# MIXR_Processing_-_ESP32.net
KiCad netlist of a schematic drawn in Altium Designer
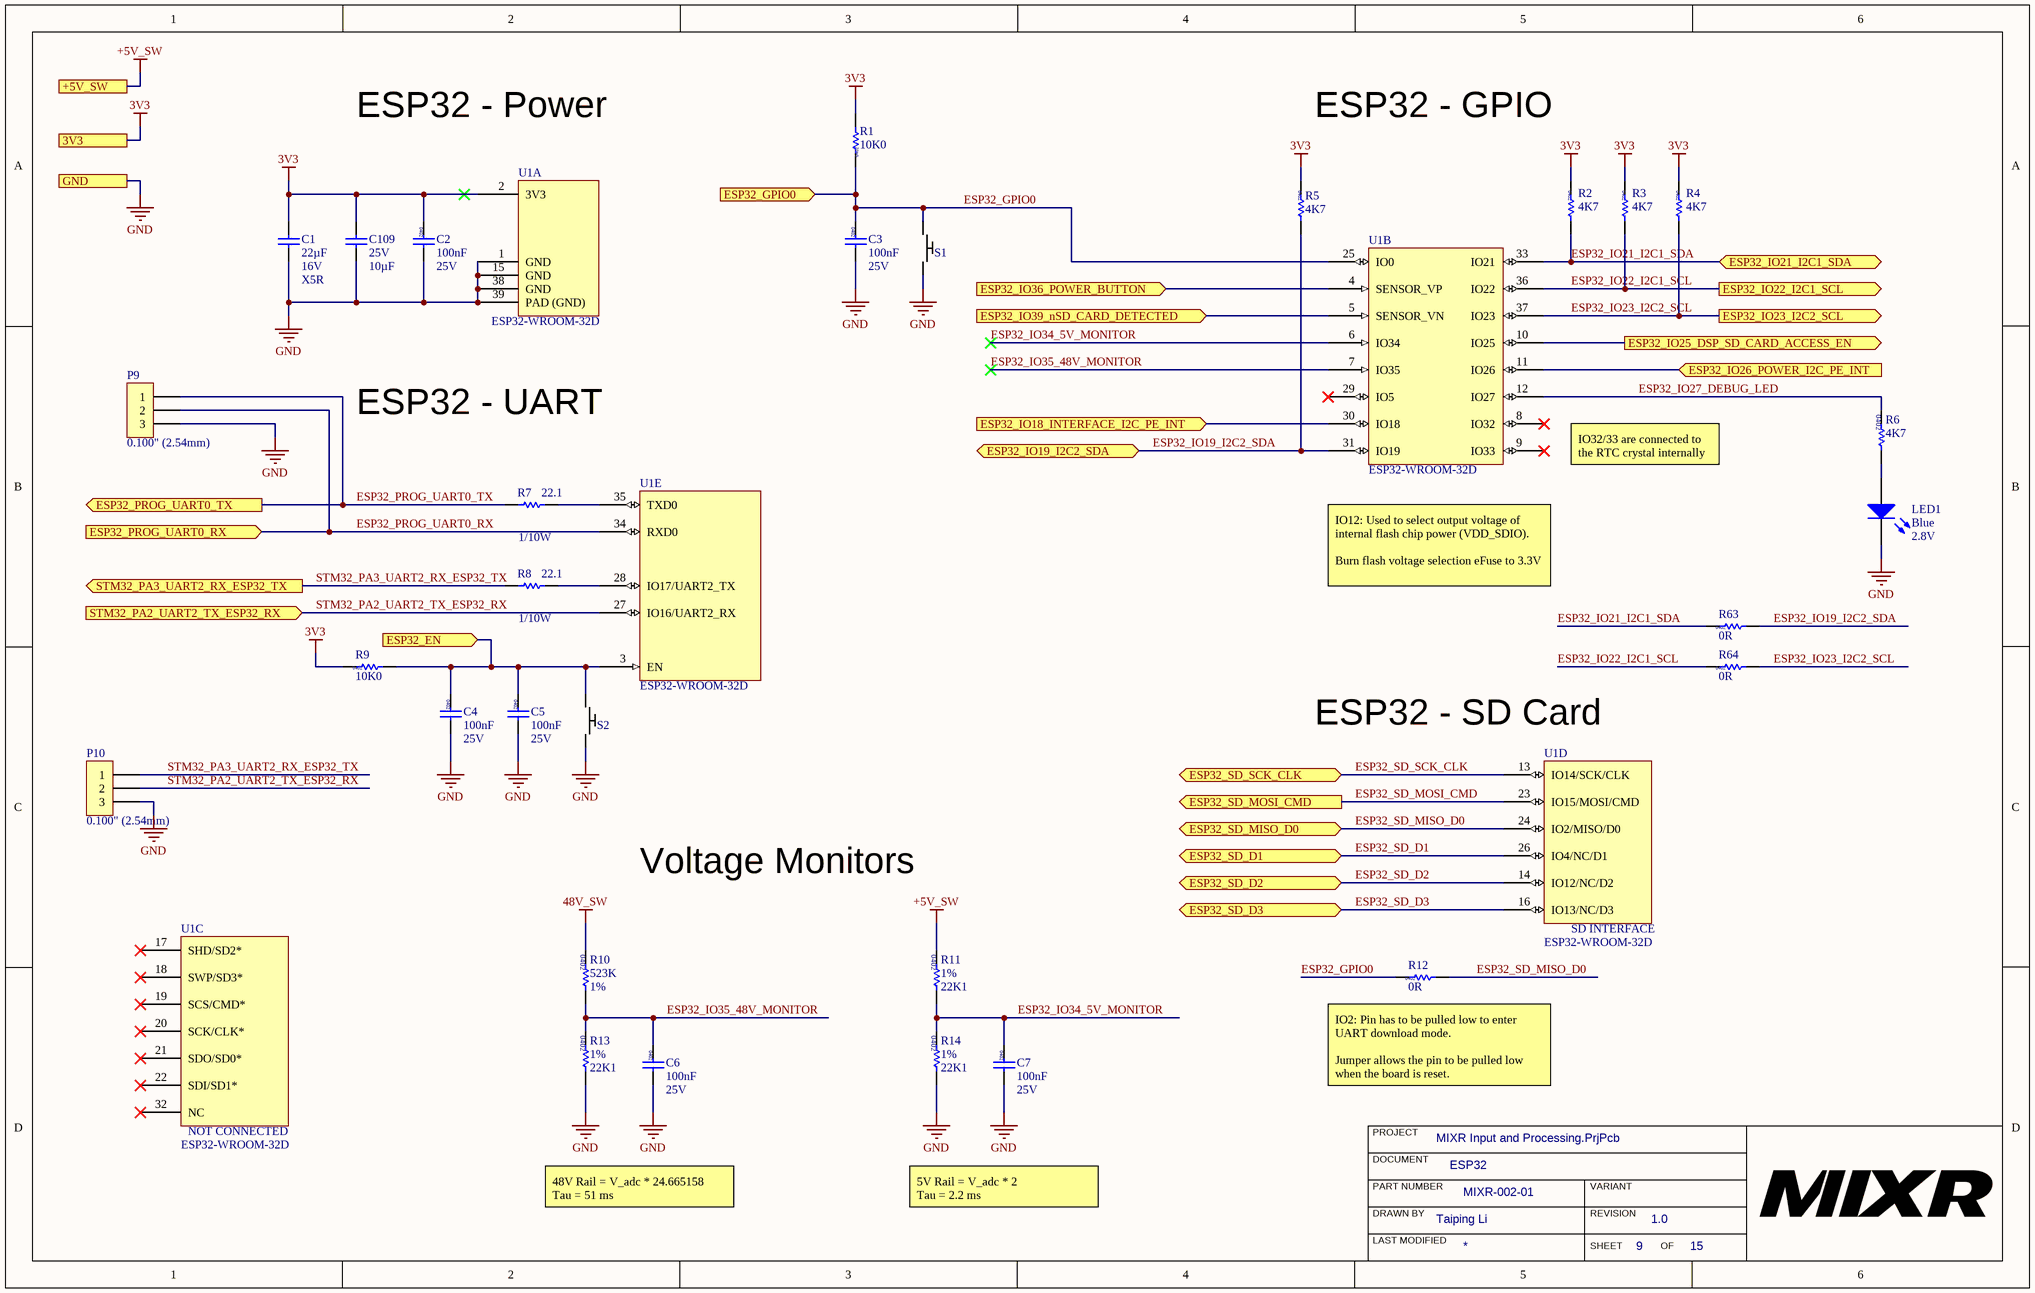
[diagram p0: MIXR Processing - ESP32.SchDoc]

(export (version "E")
  (design (tool "Eeschema 10.0.6"))
  (components
    (comp (ref "C1")
      (value "CAP CER 22UF 16V ±20% X5R 1210")
      (footprint "CAP, 1210")
      (description "22µF ±20% 16V Ceramic Capacitor X5R 1210 (3225 Metric)")
      (fields
        (field (name "TOLERANCE") "±20%")
        (field (name "CAPACITANCE") "22µF")
        (field (name "VOLTAGE") "16V")
        (field (name "TEMPERATURE COEFFICIENT") "X5R")
      )
      (libsource (lib "Schematic Diagrams") (part "CAP CER 22UF 16V ±20% X5R 1210"))
    )
    (comp (ref "C2")
      (value "CAP CER 0.1UF 16V X7R 0402")
      (footprint "CAP 0402")
      (description "Cap Ceramic 0.1uF 25V X7R 10% SMD 0402 125C Paper T/R")
      (fields
        (field (name "TOLERANCE") "10%")
        (field (name "CAPACITANCE") "100nF")
        (field (name "VOLTAGE") "25V")
        (field (name "MANUFACTURER") "Murata")
      )
      (libsource (lib "Schematic Diagrams") (part "CAP CER 0.1UF 16V X7R 0402"))
    )
    (comp (ref "C3")
      (value "CAP CER 0.1UF 16V X7R 0402")
      (footprint "CAP 0402")
      (description "Cap Ceramic 0.1uF 25V X7R 10% SMD 0402 125C Paper T/R")
      (fields
        (field (name "TOLERANCE") "10%")
        (field (name "CAPACITANCE") "100nF")
        (field (name "VOLTAGE") "25V")
        (field (name "MANUFACTURER") "Murata")
      )
      (libsource (lib "Schematic Diagrams") (part "CAP CER 0.1UF 16V X7R 0402"))
    )
    (comp (ref "C4")
      (value "CAP CER 0.1UF 16V X7R 0402")
      (footprint "CAP 0402")
      (description "Cap Ceramic 0.1uF 25V X7R 10% SMD 0402 125C Paper T/R")
      (fields
        (field (name "TOLERANCE") "10%")
        (field (name "CAPACITANCE") "100nF")
        (field (name "VOLTAGE") "25V")
        (field (name "MANUFACTURER") "Murata")
      )
      (libsource (lib "Schematic Diagrams") (part "CAP CER 0.1UF 16V X7R 0402"))
    )
    (comp (ref "C5")
      (value "CAP CER 0.1UF 16V X7R 0402")
      (footprint "CAP 0402")
      (description "Cap Ceramic 0.1uF 25V X7R 10% SMD 0402 125C Paper T/R")
      (fields
        (field (name "TOLERANCE") "10%")
        (field (name "CAPACITANCE") "100nF")
        (field (name "VOLTAGE") "25V")
        (field (name "MANUFACTURER") "Murata")
      )
      (libsource (lib "Schematic Diagrams") (part "CAP CER 0.1UF 16V X7R 0402"))
    )
    (comp (ref "C6")
      (value "CAP CER 0.1UF 16V X7R 0402")
      (footprint "CAP 0402")
      (description "Cap Ceramic 0.1uF 25V X7R 10% SMD 0402 125C Paper T/R")
      (fields
        (field (name "TOLERANCE") "10%")
        (field (name "CAPACITANCE") "100nF")
        (field (name "VOLTAGE") "25V")
        (field (name "MANUFACTURER") "Murata")
      )
      (libsource (lib "Schematic Diagrams") (part "CAP CER 0.1UF 16V X7R 0402"))
    )
    (comp (ref "C7")
      (value "CAP CER 0.1UF 16V X7R 0402")
      (footprint "CAP 0402")
      (description "Cap Ceramic 0.1uF 25V X7R 10% SMD 0402 125C Paper T/R")
      (fields
        (field (name "TOLERANCE") "10%")
        (field (name "CAPACITANCE") "100nF")
        (field (name "VOLTAGE") "25V")
        (field (name "MANUFACTURER") "Murata")
      )
      (libsource (lib "Schematic Diagrams") (part "CAP CER 0.1UF 16V X7R 0402"))
    )
    (comp (ref "C109")
      (value "CAP CER 10uF 25V 10% X5R 0805")
      (footprint "CAP, 0805")
      (description "10µF ±10% 25V Ceramic Capacitor X5R 0805 (2012 Metric)")
      (fields
        (field (name "MANUFACTURER") "Murata Electronics North America")
        (field (name "MANUFACTURER PART NUMBER") "GRM21BR61E106KA73L")
        (field (name "VOLTAGE - RATED") "25V")
        (field (name "CAPACITANCE") "10µF")
      )
      (libsource (lib "Schematic Diagrams") (part "CAP CER 10uF 25V 10% X5R 0805"))
    )
    (comp (ref "LED1")
      (value "LED BLUE CLEAR 2.8V 0603")
      (footprint "LED_0603")
      (description "Blue 470nm LED Indication - Discrete 2.8V 0603 (1608 Metric)")
      (fields (field (name "COLOR") "Blue") (field (name "VOLTAGE - FORWARD (VF) (TYP)") "2.8V"))
      (libsource (lib "Schematic Diagrams") (part "LED BLUE CLEAR 2.8V 0603"))
    )
    (comp (ref "P9")
      (value "CONN 3POS HEADR MALE 0.1\"")
      (footprint "CONN, 3POS 0.100\" Header, 1 ROW")
      (description "3 Positions Header Connector 0.100\" (2.54mm) Through Hole Gold")
      (fields (field (name "VOLTAGE") "250V") (field (name "PITCH - MATING") "0.100\" (2.54mm)"))
      (libsource (lib "Schematic Diagrams") (part "CONN 3POS HEADR MALE 0.1{dblquote}"))
    )
    (comp (ref "P10")
      (value "CONN 3POS HEADR MALE 0.1\"")
      (footprint "CONN, 3POS 0.100\" Header, 1 ROW")
      (description "3 Positions Header Connector 0.100\" (2.54mm) Through Hole Gold")
      (fields (field (name "VOLTAGE") "250V") (field (name "PITCH - MATING") "0.100\" (2.54mm)"))
      (libsource (lib "Schematic Diagrams") (part "CONN 3POS HEADR MALE 0.1{dblquote}"))
    )
    (comp (ref "R1")
      (value "RES 10K OHM 1% 1/16W 0402")
      (footprint "RES 0402")
      (description "Surface Mount Thick Film Resistor, Rc Series, 10 Kohm, 62.5 Mw, - 1%, 50 V, 0402 [1005 Metric]")
      (fields
        (field (name "TOLERANCE") "1%")
        (field (name "RESISTANCE") "10K0")
        (field (name "MANUFACTURER") "Yageo")
      )
      (libsource (lib "Schematic Diagrams") (part "RES 10K OHM 1% 1/16W 0402"))
    )
    (comp (ref "R2")
      (value "RES 4.7K OHM 1% 1/10W 0402")
      (footprint "RES 0402")
      (description "YAGEO (PHYCOMP) - RC0402FR-074K7L - RES, THICK FILM, 4K7, 1%, 0.063W, 0402")
      (fields
        (field (name "TOLERANCE") "1%")
        (field (name "MANUFACTURER") "Yageo")
        (field (name "RESISTANCE") "4K7")
      )
      (libsource (lib "Schematic Diagrams") (part "RES 4.7K OHM 1% 1/10W 0402"))
    )
    (comp (ref "R3")
      (value "RES 4.7K OHM 1% 1/10W 0402")
      (footprint "RES 0402")
      (description "YAGEO (PHYCOMP) - RC0402FR-074K7L - RES, THICK FILM, 4K7, 1%, 0.063W, 0402")
      (fields
        (field (name "TOLERANCE") "1%")
        (field (name "MANUFACTURER") "Yageo")
        (field (name "RESISTANCE") "4K7")
      )
      (libsource (lib "Schematic Diagrams") (part "RES 4.7K OHM 1% 1/10W 0402"))
    )
    (comp (ref "R4")
      (value "RES 4.7K OHM 1% 1/10W 0402")
      (footprint "RES 0402")
      (description "YAGEO (PHYCOMP) - RC0402FR-074K7L - RES, THICK FILM, 4K7, 1%, 0.063W, 0402")
      (fields
        (field (name "TOLERANCE") "1%")
        (field (name "MANUFACTURER") "Yageo")
        (field (name "RESISTANCE") "4K7")
      )
      (libsource (lib "Schematic Diagrams") (part "RES 4.7K OHM 1% 1/10W 0402"))
    )
    (comp (ref "R5")
      (value "RES 4.7K OHM 1% 1/10W 0402")
      (footprint "RES 0402")
      (description "YAGEO (PHYCOMP) - RC0402FR-074K7L - RES, THICK FILM, 4K7, 1%, 0.063W, 0402")
      (fields
        (field (name "TOLERANCE") "1%")
        (field (name "MANUFACTURER") "Yageo")
        (field (name "RESISTANCE") "4K7")
      )
      (libsource (lib "Schematic Diagrams") (part "RES 4.7K OHM 1% 1/10W 0402"))
    )
    (comp (ref "R6")
      (value "RES 4.7K OHM 1% 1/10W 0402")
      (footprint "RES 0402")
      (description "YAGEO (PHYCOMP) - RC0402FR-074K7L - RES, THICK FILM, 4K7, 1%, 0.063W, 0402")
      (fields
        (field (name "TOLERANCE") "1%")
        (field (name "MANUFACTURER") "Yageo")
        (field (name "RESISTANCE") "4K7")
      )
      (libsource (lib "Schematic Diagrams") (part "RES 4.7K OHM 1% 1/10W 0402"))
    )
    (comp (ref "R7")
      (value "RES 22.1 OHM 1% 1/10W 0603")
      (footprint "RES, 0603")
      (description "22.1 Ohm ±1% 0.1W, 1/10W Chip Resistor 0603 (1608 Metric) Moisture Resistant Thick Film")
      (fields
        (field (name "TOLERANCE") "±1%")
        (field (name "RESISTANCE") "22.1")
        (field (name "POWER") "1/10W")
      )
      (libsource (lib "Schematic Diagrams") (part "RES 22.1 OHM 1% 1/10W 0603"))
    )
    (comp (ref "R8")
      (value "RES 22.1 OHM 1% 1/10W 0603")
      (footprint "RES, 0603")
      (description "22.1 Ohm ±1% 0.1W, 1/10W Chip Resistor 0603 (1608 Metric) Moisture Resistant Thick Film")
      (fields
        (field (name "TOLERANCE") "±1%")
        (field (name "RESISTANCE") "22.1")
        (field (name "POWER") "1/10W")
      )
      (libsource (lib "Schematic Diagrams") (part "RES 22.1 OHM 1% 1/10W 0603"))
    )
    (comp (ref "R9")
      (value "RES 10K OHM 1% 1/16W 0402")
      (footprint "RES 0402")
      (description "Surface Mount Thick Film Resistor, Rc Series, 10 Kohm, 62.5 Mw, - 1%, 50 V, 0402 [1005 Metric]")
      (fields
        (field (name "TOLERANCE") "1%")
        (field (name "RESISTANCE") "10K0")
        (field (name "MANUFACTURER") "Yageo")
      )
      (libsource (lib "Schematic Diagrams") (part "RES 10K OHM 1% 1/16W 0402"))
    )
    (comp (ref "R10")
      (value "RES 523K OHM 1% 1/16W 0402")
      (footprint "RES 0402")
      (description "Thick Film Resistors 523K OHM 1%")
      (fields
        (field (name "MANUFACTURER") "Yageo")
        (field (name "MANUFACTURER PART NUMBER") "RC0402FR-07523KL")
        (field (name "RESISTANCE") "523K")
        (field (name "TOLERANCE") "1%")
      )
      (libsource (lib "Schematic Diagrams") (part "RES 523K OHM 1% 1/16W 0402"))
    )
    (comp (ref "R11")
      (value "RES 22.1K OHM 1% 1/16W 0402")
      (footprint "RES 0402")
      (description "RES SMD 22.1K OHM 1% 1/16W 0402")
      (fields
        (field (name "MANUFACTURER") "Stackpole Electronics")
        (field (name "MANUFACTURER PART NUMBER") "RMCF0402FT22K1")
        (field (name "TOLERANCE") "1%")
        (field (name "RESISTANCE") "22K1")
      )
      (libsource (lib "Schematic Diagrams") (part "RES 22.1K OHM 1% 1/16W 0402"))
    )
    (comp (ref "R12")
      (value "RES 0.0 OHM 1% 1/16W 0402")
      (footprint "RES 0402")
      (description "RES SMD 0 OHM JUMPER 1/16W 0402")
      (fields
        (field (name "RESISTANCE") "0R")
        (field (name "MANUFACTURER") "Yageo")
        (field (name "MANUFACTURER PART NUMBER") "RC0402JR-070RL")
      )
      (libsource (lib "Schematic Diagrams") (part "RES 0.0 OHM 1% 1/16W 0402"))
    )
    (comp (ref "R13")
      (value "RES 22.1K OHM 1% 1/16W 0402")
      (footprint "RES 0402")
      (description "RES SMD 22.1K OHM 1% 1/16W 0402")
      (fields
        (field (name "MANUFACTURER") "Stackpole Electronics")
        (field (name "MANUFACTURER PART NUMBER") "RMCF0402FT22K1")
        (field (name "TOLERANCE") "1%")
        (field (name "RESISTANCE") "22K1")
      )
      (libsource (lib "Schematic Diagrams") (part "RES 22.1K OHM 1% 1/16W 0402"))
    )
    (comp (ref "R14")
      (value "RES 22.1K OHM 1% 1/16W 0402")
      (footprint "RES 0402")
      (description "RES SMD 22.1K OHM 1% 1/16W 0402")
      (fields
        (field (name "MANUFACTURER") "Stackpole Electronics")
        (field (name "MANUFACTURER PART NUMBER") "RMCF0402FT22K1")
        (field (name "TOLERANCE") "1%")
        (field (name "RESISTANCE") "22K1")
      )
      (libsource (lib "Schematic Diagrams") (part "RES 22.1K OHM 1% 1/16W 0402"))
    )
    (comp (ref "R63")
      (value "RES 0.0 OHM 1% 1/16W 0402")
      (footprint "RES 0402")
      (description "RES SMD 0 OHM JUMPER 1/16W 0402")
      (fields
        (field (name "RESISTANCE") "0R")
        (field (name "MANUFACTURER") "Yageo")
        (field (name "MANUFACTURER PART NUMBER") "RC0402JR-070RL")
      )
      (libsource (lib "Schematic Diagrams") (part "RES 0.0 OHM 1% 1/16W 0402"))
    )
    (comp (ref "R64")
      (value "RES 0.0 OHM 1% 1/16W 0402")
      (footprint "RES 0402")
      (description "RES SMD 0 OHM JUMPER 1/16W 0402")
      (fields
        (field (name "RESISTANCE") "0R")
        (field (name "MANUFACTURER") "Yageo")
        (field (name "MANUFACTURER PART NUMBER") "RC0402JR-070RL")
      )
      (libsource (lib "Schematic Diagrams") (part "RES 0.0 OHM 1% 1/16W 0402"))
    )
    (comp (ref "S1")
      (value "SPST")
      (footprint "SW SPST-NO 0.05A 12V")
      (description "SWITCH TACTILE SPST-NO 50MA 12V")
      (fields
        (field (name "MANUFACTURER") "E-Switch")
        (field (name "MANUFACTURER PART NUMBER") "TL3305AF260QG")
      )
      (libsource (lib "Schematic Diagrams") (part "SW SPST-NO 0.05A 12V"))
    )
    (comp (ref "S2")
      (value "SPST")
      (footprint "SW SPST-NO 0.05A 12V")
      (description "SWITCH TACTILE SPST-NO 50MA 12V")
      (fields
        (field (name "MANUFACTURER") "E-Switch")
        (field (name "MANUFACTURER PART NUMBER") "TL3305AF260QG")
      )
      (libsource (lib "Schematic Diagrams") (part "SW SPST-NO 0.05A 12V"))
    )
    (comp (ref "U1")
      (value "ESP32-WROOM-32D")
      (footprint "IC WIFI MODULE 32MBITS SPI FLASH")
      (description "WIFI MODULE 32MBITS SPI FLASH")
      (fields
        (field (name "MANUFACTURER") "Espressif Systems")
        (field (name "MANUFACTURER PART NUMBER") "ESP32-WROOM-32D")
      )
      (libsource (lib "Schematic Diagrams") (part "IC WIFI MODULE 32MBITS SPI FLASH"))
    )
  )
  (nets
    (net (code "1") (name "+5V_SW") (class "Default")
      (node (ref "R11") (pin "1") (pinfunction "1_1") (pintype "passive"))
    )
    (net (code "2") (name "/ESP32_EN") (class "Default")
      (node (ref "C4") (pin "1") (pinfunction "1_1") (pintype "passive"))
      (node (ref "C5") (pin "1") (pinfunction "1_1") (pintype "passive"))
      (node (ref "R9") (pin "2") (pinfunction "2_2") (pintype "passive"))
      (node (ref "S2") (pin "1") (pinfunction "1_1") (pintype "passive"))
      (node (ref "U1") (pin "3") (pinfunction "EN_3") (pintype "input"))
    )
    (net (code "3") (name "/ESP32_GPIO0") (class "Default")
      (node (ref "C3") (pin "1") (pinfunction "1_1") (pintype "passive"))
      (node (ref "R1") (pin "1") (pinfunction "1_1") (pintype "passive"))
      (node (ref "R12") (pin "1") (pinfunction "1_1") (pintype "passive"))
      (node (ref "S1") (pin "1") (pinfunction "1_1") (pintype "passive"))
      (node (ref "U1") (pin "25") (pinfunction "IO0_25") (pintype "bidirectional"))
    )
    (net (code "4") (name "/ESP32_IO18_INTERFACE_I2C_PE_INT") (class "Default")
      (node (ref "U1") (pin "30") (pinfunction "IO18_30") (pintype "bidirectional"))
    )
    (net (code "5") (name "/ESP32_IO19_I2C2_SDA") (class "Default")
      (node (ref "R5") (pin "2") (pinfunction "2_2") (pintype "passive"))
      (node (ref "R63") (pin "2") (pinfunction "2_2") (pintype "passive"))
      (node (ref "U1") (pin "31") (pinfunction "IO19_31") (pintype "bidirectional"))
    )
    (net (code "6") (name "/ESP32_IO21_I2C1_SDA") (class "Default")
      (node (ref "R2") (pin "2") (pinfunction "2_2") (pintype "passive"))
      (node (ref "R63") (pin "1") (pinfunction "1_1") (pintype "passive"))
      (node (ref "U1") (pin "33") (pinfunction "IO21_33") (pintype "bidirectional"))
    )
    (net (code "7") (name "/ESP32_IO22_I2C1_SCL") (class "Default")
      (node (ref "R3") (pin "2") (pinfunction "2_2") (pintype "passive"))
      (node (ref "R64") (pin "1") (pinfunction "1_1") (pintype "passive"))
      (node (ref "U1") (pin "36") (pinfunction "IO22_36") (pintype "bidirectional"))
    )
    (net (code "8") (name "/ESP32_IO23_I2C2_SCL") (class "Default")
      (node (ref "R4") (pin "2") (pinfunction "2_2") (pintype "passive"))
      (node (ref "R64") (pin "2") (pinfunction "2_2") (pintype "passive"))
      (node (ref "U1") (pin "37") (pinfunction "IO23_37") (pintype "bidirectional"))
    )
    (net (code "9") (name "/ESP32_IO25_DSP_SD_CARD_ACCESS_EN") (class "Default")
      (node (ref "U1") (pin "10") (pinfunction "IO25_10") (pintype "bidirectional"))
    )
    (net (code "10") (name "/ESP32_IO26_POWER_I2C_PE_INT") (class "Default")
      (node (ref "U1") (pin "11") (pinfunction "IO26_11") (pintype "bidirectional"))
    )
    (net (code "11") (name "/ESP32_IO27_DEBUG_LED") (class "Default")
      (node (ref "R6") (pin "1") (pinfunction "1_1") (pintype "passive"))
      (node (ref "U1") (pin "12") (pinfunction "IO27_12") (pintype "bidirectional"))
    )
    (net (code "12") (name "/ESP32_IO34_5V_MONITOR") (class "Default")
      (node (ref "C7") (pin "1") (pinfunction "1_1") (pintype "passive"))
      (node (ref "R11") (pin "2") (pinfunction "2_2") (pintype "passive"))
      (node (ref "R14") (pin "1") (pinfunction "1_1") (pintype "passive"))
      (node (ref "U1") (pin "6") (pinfunction "IO34_6") (pintype "input"))
    )
    (net (code "13") (name "/ESP32_IO35_48V_MONITOR") (class "Default")
      (node (ref "C6") (pin "1") (pinfunction "1_1") (pintype "passive"))
      (node (ref "R10") (pin "2") (pinfunction "2_2") (pintype "passive"))
      (node (ref "R13") (pin "1") (pinfunction "1_1") (pintype "passive"))
      (node (ref "U1") (pin "7") (pinfunction "IO35_7") (pintype "input"))
    )
    (net (code "14") (name "/ESP32_IO36_POWER_BUTTON") (class "Default")
      (node (ref "U1") (pin "4") (pinfunction "SENSOR_VP_4") (pintype "input"))
    )
    (net (code "15") (name "/ESP32_IO39_nSD_CARD_DETECTED") (class "Default")
      (node (ref "U1") (pin "5") (pinfunction "SENSOR_VN_5") (pintype "input"))
    )
    (net (code "16") (name "/ESP32_PROG_UART0_RX") (class "Default")
      (node (ref "P9") (pin "2") (pinfunction "2_2") (pintype "passive"))
      (node (ref "U1") (pin "34") (pinfunction "RXD0_34") (pintype "bidirectional"))
    )
    (net (code "17") (name "/ESP32_PROG_UART0_TX") (class "Default")
      (node (ref "P9") (pin "1") (pinfunction "1_1") (pintype "passive"))
      (node (ref "R7") (pin "1") (pinfunction "1_1") (pintype "passive"))
    )
    (net (code "18") (name "/ESP32_SD_D1") (class "Default")
      (node (ref "U1") (pin "26") (pinfunction "IO4/NC/D1_26") (pintype "bidirectional"))
    )
    (net (code "19") (name "/ESP32_SD_D2") (class "Default")
      (node (ref "U1") (pin "14") (pinfunction "IO12/NC/D2_14") (pintype "bidirectional"))
    )
    (net (code "20") (name "/ESP32_SD_D3") (class "Default")
      (node (ref "U1") (pin "16") (pinfunction "IO13/NC/D3_16") (pintype "bidirectional"))
    )
    (net (code "21") (name "/ESP32_SD_MISO_D0") (class "Default")
      (node (ref "R12") (pin "2") (pinfunction "2_2") (pintype "passive"))
      (node (ref "U1") (pin "24") (pinfunction "IO2/MISO/D0_24") (pintype "bidirectional"))
    )
    (net (code "22") (name "/ESP32_SD_MOSI_CMD") (class "Default")
      (node (ref "U1") (pin "23") (pinfunction "IO15/MOSI/CMD_23") (pintype "bidirectional"))
    )
    (net (code "23") (name "/ESP32_SD_SCK_CLK") (class "Default")
      (node (ref "U1") (pin "13") (pinfunction "IO14/SCK/CLK_13") (pintype "bidirectional"))
    )
    (net (code "24") (name "/STM32_PA2_UART2_TX_ESP32_RX") (class "Default")
      (node (ref "P10") (pin "2") (pinfunction "2_2") (pintype "passive"))
      (node (ref "U1") (pin "27") (pinfunction "IO16/UART2_RX_27") (pintype "bidirectional"))
    )
    (net (code "25") (name "/STM32_PA3_UART2_RX_ESP32_TX") (class "Default")
      (node (ref "P10") (pin "1") (pinfunction "1_1") (pintype "passive"))
      (node (ref "R8") (pin "1") (pinfunction "1_1") (pintype "passive"))
    )
    (net (code "26") (name "3V3") (class "Default")
      (node (ref "C1") (pin "1") (pinfunction "1_1") (pintype "passive"))
      (node (ref "C109") (pin "1") (pinfunction "1_1") (pintype "passive"))
      (node (ref "C2") (pin "1") (pinfunction "1_1") (pintype "passive"))
      (node (ref "R1") (pin "2") (pinfunction "2_2") (pintype "passive"))
      (node (ref "R2") (pin "1") (pinfunction "1_1") (pintype "passive"))
      (node (ref "R3") (pin "1") (pinfunction "1_1") (pintype "passive"))
      (node (ref "R4") (pin "1") (pinfunction "1_1") (pintype "passive"))
      (node (ref "R5") (pin "1") (pinfunction "1_1") (pintype "passive"))
      (node (ref "R9") (pin "1") (pinfunction "1_1") (pintype "passive"))
      (node (ref "U1") (pin "2") (pinfunction "3V3_2") (pintype "power_in"))
    )
    (net (code "27") (name "48V_SW") (class "Default")
      (node (ref "R10") (pin "1") (pinfunction "1_1") (pintype "passive"))
    )
    (net (code "28") (name "GND") (class "Default")
      (node (ref "C1") (pin "2") (pinfunction "2_2") (pintype "passive"))
      (node (ref "C109") (pin "2") (pinfunction "2_2") (pintype "passive"))
      (node (ref "C2") (pin "2") (pinfunction "2_2") (pintype "passive"))
      (node (ref "C3") (pin "2") (pinfunction "2_2") (pintype "passive"))
      (node (ref "C4") (pin "2") (pinfunction "2_2") (pintype "passive"))
      (node (ref "C5") (pin "2") (pinfunction "2_2") (pintype "passive"))
      (node (ref "C6") (pin "2") (pinfunction "2_2") (pintype "passive"))
      (node (ref "C7") (pin "2") (pinfunction "2_2") (pintype "passive"))
      (node (ref "LED1") (pin "2") (pinfunction "K_2") (pintype "passive"))
      (node (ref "P10") (pin "3") (pinfunction "3_3") (pintype "passive"))
      (node (ref "P9") (pin "3") (pinfunction "3_3") (pintype "passive"))
      (node (ref "R13") (pin "2") (pinfunction "2_2") (pintype "passive"))
      (node (ref "R14") (pin "2") (pinfunction "2_2") (pintype "passive"))
      (node (ref "S1") (pin "2") (pinfunction "2_2") (pintype "passive"))
      (node (ref "S2") (pin "2") (pinfunction "2_2") (pintype "passive"))
      (node (ref "U1") (pin "1") (pinfunction "GND_1") (pintype "power_in"))
      (node (ref "U1") (pin "15") (pinfunction "GND_15") (pintype "power_in"))
      (node (ref "U1") (pin "38") (pinfunction "GND_38") (pintype "power_in"))
      (node (ref "U1") (pin "39") (pinfunction "PAD_(GND)_39") (pintype "power_in"))
    )
    (net (code "29") (name "Net-(LED1-A)") (class "Default")
      (node (ref "LED1") (pin "1") (pinfunction "A_1") (pintype "passive"))
      (node (ref "R6") (pin "2") (pinfunction "2_2") (pintype "passive"))
    )
    (net (code "30") (name "Net-(U1E-IO17{slash}UART2_TX)") (class "Default")
      (node (ref "R8") (pin "2") (pinfunction "2_2") (pintype "passive"))
      (node (ref "U1") (pin "28") (pinfunction "IO17/UART2_TX_28") (pintype "bidirectional"))
    )
    (net (code "31") (name "Net-(U1E-TXD0)") (class "Default")
      (node (ref "R7") (pin "2") (pinfunction "2_2") (pintype "passive"))
      (node (ref "U1") (pin "35") (pinfunction "TXD0_35") (pintype "bidirectional"))
    )
    (net (code "32") (name "unconnected-(U1B-IO5-Pad29)") (class "Default")
      (node (ref "U1") (pin "29") (pinfunction "IO5_29") (pintype "bidirectional+no_connect"))
    )
    (net (code "33") (name "unconnected-(U1B-IO32-Pad8)") (class "Default")
      (node (ref "U1") (pin "8") (pinfunction "IO32_8") (pintype "bidirectional+no_connect"))
    )
    (net (code "34") (name "unconnected-(U1B-IO33-Pad9)") (class "Default")
      (node (ref "U1") (pin "9") (pinfunction "IO33_9") (pintype "bidirectional+no_connect"))
    )
    (net (code "35") (name "unconnected-(U1C-NC-Pad32)") (class "Default")
      (node (ref "U1") (pin "32") (pinfunction "NC_32") (pintype "passive+no_connect"))
    )
    (net (code "36") (name "unconnected-(U1C-SCK{slash}CLK*-Pad20)") (class "Default")
      (node (ref "U1") (pin "20") (pinfunction "SCK/CLK*_20") (pintype "passive+no_connect"))
    )
    (net (code "37") (name "unconnected-(U1C-SCS{slash}CMD*-Pad19)") (class "Default")
      (node (ref "U1") (pin "19") (pinfunction "SCS/CMD*_19") (pintype "passive+no_connect"))
    )
    (net (code "38") (name "unconnected-(U1C-SDI{slash}SD1*-Pad22)") (class "Default")
      (node (ref "U1") (pin "22") (pinfunction "SDI/SD1*_22") (pintype "passive+no_connect"))
    )
    (net (code "39") (name "unconnected-(U1C-SDO{slash}SD0*-Pad21)") (class "Default")
      (node (ref "U1") (pin "21") (pinfunction "SDO/SD0*_21") (pintype "passive+no_connect"))
    )
    (net (code "40") (name "unconnected-(U1C-SHD{slash}SD2*-Pad17)") (class "Default")
      (node (ref "U1") (pin "17") (pinfunction "SHD/SD2*_17") (pintype "passive+no_connect"))
    )
    (net (code "41") (name "unconnected-(U1C-SWP{slash}SD3*-Pad18)") (class "Default")
      (node (ref "U1") (pin "18") (pinfunction "SWP/SD3*_18") (pintype "passive+no_connect"))
    )
  )
)
